# PCIe_MUX_CLK.net
KiCad netlist of a schematic drawn in Altium Designer
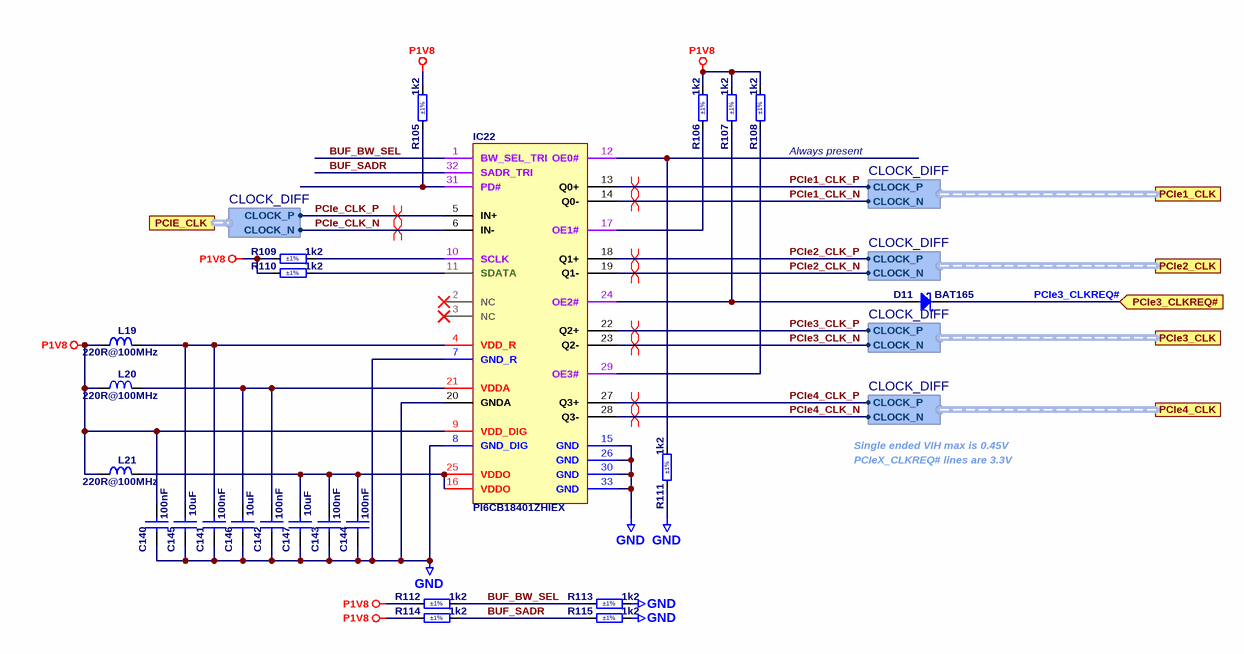
[diagram p0: PCIe_MUX_CLK.SchDoc]

(export (version "E")
  (design (tool "Eeschema 10.0.6"))
  (components
    (comp (ref "C140")
      (value "100nF")
      (footprint "CAPC1005X55N")
      (description "Non-polarised capacitor")
      (fields
        (field (name "PART NUMBER") "CC0402_100NF_16V_10%_X7R")
        (field (name "VOLTAGE") "16V")
        (field (name "AUTHOR") "CERN DEM JLC")
      )
      (libsource (lib "Capacitors") (part "Capacitor - non polarized"))
    )
    (comp (ref "C141")
      (value "100nF")
      (footprint "CAPC1005X55N")
      (description "Non-polarised capacitor")
      (fields
        (field (name "PART NUMBER") "CC0402_100NF_16V_10%_X7R")
        (field (name "VOLTAGE") "16V")
        (field (name "AUTHOR") "CERN DEM JLC")
      )
      (libsource (lib "Capacitors") (part "Capacitor - non polarized"))
    )
    (comp (ref "C142")
      (value "100nF")
      (footprint "CAPC1005X55N")
      (description "Non-polarised capacitor")
      (fields
        (field (name "PART NUMBER") "CC0402_100NF_16V_10%_X7R")
        (field (name "VOLTAGE") "16V")
        (field (name "AUTHOR") "CERN DEM JLC")
      )
      (libsource (lib "Capacitors") (part "Capacitor - non polarized"))
    )
    (comp (ref "C143")
      (value "100nF")
      (footprint "CAPC1005X55N")
      (description "Non-polarised capacitor")
      (fields
        (field (name "PART NUMBER") "CC0402_100NF_16V_10%_X7R")
        (field (name "VOLTAGE") "16V")
        (field (name "AUTHOR") "CERN DEM JLC")
      )
      (libsource (lib "Capacitors") (part "Capacitor - non polarized"))
    )
    (comp (ref "C144")
      (value "100nF")
      (footprint "CAPC1005X55N")
      (description "Non-polarised capacitor")
      (fields
        (field (name "PART NUMBER") "CC0402_100NF_16V_10%_X7R")
        (field (name "VOLTAGE") "16V")
        (field (name "AUTHOR") "CERN DEM JLC")
      )
      (libsource (lib "Capacitors") (part "Capacitor - non polarized"))
    )
    (comp (ref "C145")
      (value "10uF")
      (footprint "CAPC1608X80N")
      (description "Non-polarised capacitor")
      (fields
        (field (name "PART NUMBER") "CC0603_10UF_16V_20%_X5R")
        (field (name "VOLTAGE") "16V")
        (field (name "AUTHOR") "CERN DEM MR")
      )
      (libsource (lib "Capacitors") (part "Capacitor - non polarized"))
    )
    (comp (ref "C146")
      (value "10uF")
      (footprint "CAPC1608X80N")
      (description "Non-polarised capacitor")
      (fields
        (field (name "PART NUMBER") "CC0603_10UF_16V_20%_X5R")
        (field (name "VOLTAGE") "16V")
        (field (name "AUTHOR") "CERN DEM MR")
      )
      (libsource (lib "Capacitors") (part "Capacitor - non polarized"))
    )
    (comp (ref "C147")
      (value "10uF")
      (footprint "CAPC1608X80N")
      (description "Non-polarised capacitor")
      (fields
        (field (name "PART NUMBER") "CC0603_10UF_16V_20%_X5R")
        (field (name "VOLTAGE") "16V")
        (field (name "AUTHOR") "CERN DEM MR")
      )
      (libsource (lib "Capacitors") (part "Capacitor - non polarized"))
    )
    (comp (ref "D11")
      (value "BAT165")
      (footprint "SOD2512X110N")
      (description "Schottky Diode")
      (fields
        (field (name "VOLTAGE") "40V")
        (field (name "POWER") "750mA")
        (field (name "AUTHOR") "CERN DEM JLC")
      )
      (libsource (lib "ICs And Semiconductors") (part "Diode Schottky"))
    )
    (comp (ref "IC22")
      (value "PI6CB18401ZHIEX")
      (footprint "PERICOM_32-TQFN(ZH)")
      (description "Very Low Power 4-Output PCIe Clock Buffer With On-chip Termination")
      (libsource (lib "Kasil_DIOT_x86_board") (part "PI6CB18401"))
    )
    (comp (ref "L19")
      (value "220R@100MHz")
      (footprint "INDC2012X105N")
      (description "Inductor")
      (fields
        (field (name "PART NUMBER") "IND0805_MURATA_BLM21PG221SN1D")
        (field (name "POWER") "2A")
        (field (name "AUTHOR") "CERN DEM JLC")
      )
      (libsource (lib "Inductors & Transformers") (part "Inductor"))
    )
    (comp (ref "L20")
      (value "220R@100MHz")
      (footprint "INDC2012X105N")
      (description "Inductor")
      (fields
        (field (name "PART NUMBER") "IND0805_MURATA_BLM21PG221SN1D")
        (field (name "POWER") "2A")
        (field (name "AUTHOR") "CERN DEM JLC")
      )
      (libsource (lib "Inductors & Transformers") (part "Inductor"))
    )
    (comp (ref "L21")
      (value "220R@100MHz")
      (footprint "INDC2012X105N")
      (description "Inductor")
      (fields
        (field (name "PART NUMBER") "IND0805_MURATA_BLM21PG221SN1D")
        (field (name "POWER") "2A")
        (field (name "AUTHOR") "CERN DEM JLC")
      )
      (libsource (lib "Inductors & Transformers") (part "Inductor"))
    )
    (comp (ref "R105")
      (value "1k2")
      (footprint "RESC1005X40N")
      (description "Resistor - 1%")
      (fields
        (field (name "TOLERANCE") "±1%")
        (field (name "PART NUMBER") "R0402_1K2_1%_0.0625W_100PPM")
        (field (name "POWER") "0.0625W")
        (field (name "AUTHOR") "CERN DEM JLC")
      )
      (libsource (lib "Resistors") (part "Resistor - 1%"))
    )
    (comp (ref "R106")
      (value "1k2")
      (footprint "RESC1005X40N")
      (description "Resistor - 1%")
      (fields
        (field (name "TOLERANCE") "±1%")
        (field (name "PART NUMBER") "R0402_1K2_1%_0.0625W_100PPM")
        (field (name "POWER") "0.0625W")
        (field (name "AUTHOR") "CERN DEM JLC")
      )
      (libsource (lib "Resistors") (part "Resistor - 1%"))
    )
    (comp (ref "R107")
      (value "1k2")
      (footprint "RESC1005X40N")
      (description "Resistor - 1%")
      (fields
        (field (name "TOLERANCE") "±1%")
        (field (name "PART NUMBER") "R0402_1K2_1%_0.0625W_100PPM")
        (field (name "POWER") "0.0625W")
        (field (name "AUTHOR") "CERN DEM JLC")
      )
      (libsource (lib "Resistors") (part "Resistor - 1%"))
    )
    (comp (ref "R108")
      (value "1k2")
      (footprint "RESC1005X40N")
      (description "Resistor - 1%")
      (fields
        (field (name "TOLERANCE") "±1%")
        (field (name "PART NUMBER") "R0402_1K2_1%_0.0625W_100PPM")
        (field (name "POWER") "0.0625W")
        (field (name "AUTHOR") "CERN DEM JLC")
      )
      (libsource (lib "Resistors") (part "Resistor - 1%"))
    )
    (comp (ref "R109")
      (value "1k2")
      (footprint "RESC1005X40N")
      (description "Resistor - 1%")
      (fields
        (field (name "TOLERANCE") "±1%")
        (field (name "PART NUMBER") "R0402_1K2_1%_0.0625W_100PPM")
        (field (name "POWER") "0.0625W")
        (field (name "AUTHOR") "CERN DEM JLC")
      )
      (libsource (lib "Resistors") (part "Resistor - 1%"))
    )
    (comp (ref "R110")
      (value "1k2")
      (footprint "RESC1005X40N")
      (description "Resistor - 1%")
      (fields
        (field (name "TOLERANCE") "±1%")
        (field (name "PART NUMBER") "R0402_1K2_1%_0.0625W_100PPM")
        (field (name "POWER") "0.0625W")
        (field (name "AUTHOR") "CERN DEM JLC")
      )
      (libsource (lib "Resistors") (part "Resistor - 1%"))
    )
    (comp (ref "R111")
      (value "1k2")
      (footprint "RESC1005X40N")
      (description "Resistor - 1%")
      (fields
        (field (name "TOLERANCE") "±1%")
        (field (name "PART NUMBER") "R0402_1K2_1%_0.0625W_100PPM")
        (field (name "POWER") "0.0625W")
        (field (name "AUTHOR") "CERN DEM JLC")
      )
      (libsource (lib "Resistors") (part "Resistor - 1%"))
    )
    (comp (ref "R112")
      (value "1k2")
      (footprint "RESC1005X40N")
      (description "Resistor - 1%")
      (fields
        (field (name "TOLERANCE") "±1%")
        (field (name "PART NUMBER") "R0402_1K2_1%_0.0625W_100PPM")
        (field (name "POWER") "0.0625W")
        (field (name "AUTHOR") "CERN DEM JLC")
      )
      (libsource (lib "Resistors") (part "Resistor - 1%"))
    )
    (comp (ref "R113")
      (value "1k2")
      (footprint "RESC1005X40N")
      (description "Resistor - 1%")
      (fields
        (field (name "TOLERANCE") "±1%")
        (field (name "PART NUMBER") "R0402_1K2_1%_0.0625W_100PPM")
        (field (name "POWER") "0.0625W")
        (field (name "AUTHOR") "CERN DEM JLC")
      )
      (libsource (lib "Resistors") (part "Resistor - 1%"))
    )
    (comp (ref "R114")
      (value "1k2")
      (footprint "RESC1005X40N")
      (description "Resistor - 1%")
      (fields
        (field (name "TOLERANCE") "±1%")
        (field (name "PART NUMBER") "R0402_1K2_1%_0.0625W_100PPM")
        (field (name "POWER") "0.0625W")
        (field (name "AUTHOR") "CERN DEM JLC")
      )
      (libsource (lib "Resistors") (part "Resistor - 1%"))
    )
    (comp (ref "R115")
      (value "1k2")
      (footprint "RESC1005X40N")
      (description "Resistor - 1%")
      (fields
        (field (name "TOLERANCE") "±1%")
        (field (name "PART NUMBER") "R0402_1K2_1%_0.0625W_100PPM")
        (field (name "POWER") "0.0625W")
        (field (name "AUTHOR") "CERN DEM JLC")
      )
      (libsource (lib "Resistors") (part "Resistor - 1%"))
    )
  )
  (nets
    (net (code "2") (name "/BUF_BW_SEL") (class "Default")
      (node (ref "IC22") (pin "1") (pinfunction "BW_SEL_TRI_1") (pintype "passive"))
      (node (ref "R112") (pin "2") (pinfunction "2_2") (pintype "passive"))
      (node (ref "R113") (pin "1") (pinfunction "1_1") (pintype "passive"))
    )
    (net (code "3") (name "/BUF_SADR") (class "Default")
      (node (ref "IC22") (pin "32") (pinfunction "SADR_TRI_32") (pintype "passive"))
      (node (ref "R114") (pin "2") (pinfunction "2_2") (pintype "passive"))
      (node (ref "R115") (pin "1") (pinfunction "1_1") (pintype "passive"))
    )
    (net (code "4") (name "/PCIe1_CLK_N") (class "Default")
      (node (ref "IC22") (pin "14") (pinfunction "Q0-_14") (pintype "passive"))
    )
    (net (code "5") (name "/PCIe1_CLK_P") (class "Default")
      (node (ref "IC22") (pin "13") (pinfunction "Q0+_13") (pintype "passive"))
    )
    (net (code "6") (name "/PCIe2_CLK_N") (class "Default")
      (node (ref "IC22") (pin "19") (pinfunction "Q1-_19") (pintype "passive"))
    )
    (net (code "7") (name "/PCIe2_CLK_P") (class "Default")
      (node (ref "IC22") (pin "18") (pinfunction "Q1+_18") (pintype "passive"))
    )
    (net (code "8") (name "/PCIe3_CLKREQ#") (class "Default")
      (node (ref "D11") (pin "1") (pinfunction "C_1") (pintype "passive"))
    )
    (net (code "9") (name "/PCIe3_CLK_N") (class "Default")
      (node (ref "IC22") (pin "23") (pinfunction "Q2-_23") (pintype "passive"))
    )
    (net (code "10") (name "/PCIe3_CLK_P") (class "Default")
      (node (ref "IC22") (pin "22") (pinfunction "Q2+_22") (pintype "passive"))
    )
    (net (code "11") (name "/PCIe4_CLK_N") (class "Default")
      (node (ref "IC22") (pin "28") (pinfunction "Q3-_28") (pintype "passive"))
    )
    (net (code "12") (name "/PCIe4_CLK_P") (class "Default")
      (node (ref "IC22") (pin "27") (pinfunction "Q3+_27") (pintype "passive"))
    )
    (net (code "13") (name "/PCIe_CLK_N") (class "Default")
      (node (ref "IC22") (pin "6") (pinfunction "IN-_6") (pintype "passive"))
    )
    (net (code "14") (name "/PCIe_CLK_P") (class "Default")
      (node (ref "IC22") (pin "5") (pinfunction "IN+_5") (pintype "passive"))
    )
    (net (code "16") (name "GND") (class "Default")
      (node (ref "C140") (pin "1") (pinfunction "1_1") (pintype "passive"))
      (node (ref "C141") (pin "1") (pinfunction "1_1") (pintype "passive"))
      (node (ref "C142") (pin "1") (pinfunction "1_1") (pintype "passive"))
      (node (ref "C143") (pin "1") (pinfunction "1_1") (pintype "passive"))
      (node (ref "C144") (pin "1") (pinfunction "1_1") (pintype "passive"))
      (node (ref "C145") (pin "1") (pinfunction "1_1") (pintype "passive"))
      (node (ref "C146") (pin "1") (pinfunction "1_1") (pintype "passive"))
      (node (ref "C147") (pin "1") (pinfunction "1_1") (pintype "passive"))
      (node (ref "IC22") (pin "15") (pinfunction "GND_15") (pintype "passive"))
      (node (ref "IC22") (pin "20") (pinfunction "GNDA_20") (pintype "passive"))
      (node (ref "IC22") (pin "26") (pinfunction "GND_26") (pintype "passive"))
      (node (ref "IC22") (pin "30") (pinfunction "GND_30") (pintype "passive"))
      (node (ref "IC22") (pin "33") (pinfunction "GND_33") (pintype "passive"))
      (node (ref "IC22") (pin "7") (pinfunction "GND_R_7") (pintype "passive"))
      (node (ref "IC22") (pin "8") (pinfunction "GND_DIG_8") (pintype "passive"))
      (node (ref "R111") (pin "1") (pinfunction "1_1") (pintype "passive"))
      (node (ref "R113") (pin "2") (pinfunction "2_2") (pintype "passive"))
      (node (ref "R115") (pin "2") (pinfunction "2_2") (pintype "passive"))
    )
    (net (code "17") (name "Net-(C143-Pad2)") (class "Default")
      (node (ref "C143") (pin "2") (pinfunction "2_2") (pintype "passive"))
      (node (ref "C144") (pin "2") (pinfunction "2_2") (pintype "passive"))
      (node (ref "C147") (pin "2") (pinfunction "2_2") (pintype "passive"))
      (node (ref "IC22") (pin "16") (pinfunction "VDDO_16") (pintype "passive"))
      (node (ref "IC22") (pin "25") (pinfunction "VDDO_25") (pintype "passive"))
      (node (ref "L21") (pin "2") (pinfunction "2_2") (pintype "passive"))
    )
    (net (code "18") (name "Net-(D11-A)") (class "Default")
      (node (ref "D11") (pin "2") (pinfunction "A_2") (pintype "passive"))
      (node (ref "IC22") (pin "24") (pinfunction "OE2#_24") (pintype "passive"))
      (node (ref "R107") (pin "1") (pinfunction "1_1") (pintype "passive"))
    )
    (net (code "19") (name "Net-(IC22-OE0#)") (class "Default")
      (node (ref "IC22") (pin "12") (pinfunction "OE0#_12") (pintype "passive"))
      (node (ref "R111") (pin "2") (pinfunction "2_2") (pintype "passive"))
    )
    (net (code "20") (name "Net-(IC22-OE1#)") (class "Default")
      (node (ref "IC22") (pin "17") (pinfunction "OE1#_17") (pintype "passive"))
      (node (ref "R106") (pin "1") (pinfunction "1_1") (pintype "passive"))
    )
    (net (code "21") (name "Net-(IC22-OE3#)") (class "Default")
      (node (ref "IC22") (pin "29") (pinfunction "OE3#_29") (pintype "passive"))
      (node (ref "R108") (pin "1") (pinfunction "1_1") (pintype "passive"))
    )
    (net (code "22") (name "Net-(IC22-PD#)") (class "Default")
      (node (ref "IC22") (pin "31") (pinfunction "PD#_31") (pintype "passive"))
      (node (ref "R105") (pin "1") (pinfunction "1_1") (pintype "passive"))
    )
    (net (code "23") (name "Net-(IC22-SCLK)") (class "Default")
      (node (ref "IC22") (pin "10") (pinfunction "SCLK_10") (pintype "passive"))
      (node (ref "R109") (pin "2") (pinfunction "2_2") (pintype "passive"))
    )
    (net (code "24") (name "Net-(IC22-SDATA)") (class "Default")
      (node (ref "IC22") (pin "11") (pinfunction "SDATA_11") (pintype "passive"))
      (node (ref "R110") (pin "2") (pinfunction "2_2") (pintype "passive"))
    )
    (net (code "25") (name "Net-(IC22-VDDA)") (class "Default")
      (node (ref "C142") (pin "2") (pinfunction "2_2") (pintype "passive"))
      (node (ref "C146") (pin "2") (pinfunction "2_2") (pintype "passive"))
      (node (ref "IC22") (pin "21") (pinfunction "VDDA_21") (pintype "passive"))
      (node (ref "L20") (pin "2") (pinfunction "2_2") (pintype "passive"))
    )
    (net (code "26") (name "Net-(IC22-VDD_R)") (class "Default")
      (node (ref "C141") (pin "2") (pinfunction "2_2") (pintype "passive"))
      (node (ref "C145") (pin "2") (pinfunction "2_2") (pintype "passive"))
      (node (ref "IC22") (pin "4") (pinfunction "VDD_R_4") (pintype "passive"))
      (node (ref "L19") (pin "2") (pinfunction "2_2") (pintype "passive"))
    )
    (net (code "27") (name "P1V8") (class "Default")
      (node (ref "C140") (pin "2") (pinfunction "2_2") (pintype "passive"))
      (node (ref "IC22") (pin "9") (pinfunction "VDD_DIG_9") (pintype "passive"))
      (node (ref "L19") (pin "1") (pinfunction "1_1") (pintype "passive"))
      (node (ref "L20") (pin "1") (pinfunction "1_1") (pintype "passive"))
      (node (ref "L21") (pin "1") (pinfunction "1_1") (pintype "passive"))
      (node (ref "R105") (pin "2") (pinfunction "2_2") (pintype "passive"))
      (node (ref "R106") (pin "2") (pinfunction "2_2") (pintype "passive"))
      (node (ref "R107") (pin "2") (pinfunction "2_2") (pintype "passive"))
      (node (ref "R108") (pin "2") (pinfunction "2_2") (pintype "passive"))
      (node (ref "R109") (pin "1") (pinfunction "1_1") (pintype "passive"))
      (node (ref "R110") (pin "1") (pinfunction "1_1") (pintype "passive"))
      (node (ref "R112") (pin "1") (pinfunction "1_1") (pintype "passive"))
      (node (ref "R114") (pin "1") (pinfunction "1_1") (pintype "passive"))
    )
    (net (code "28") (name "unconnected-(IC22-NC-Pad2)") (class "Default")
      (node (ref "IC22") (pin "2") (pinfunction "NC_2") (pintype "passive+no_connect"))
    )
    (net (code "29") (name "unconnected-(IC22-NC-Pad3)") (class "Default")
      (node (ref "IC22") (pin "3") (pinfunction "NC_3") (pintype "passive+no_connect"))
    )
  )
)
